# MCU.net
KiCad netlist of a schematic drawn in Altium Designer
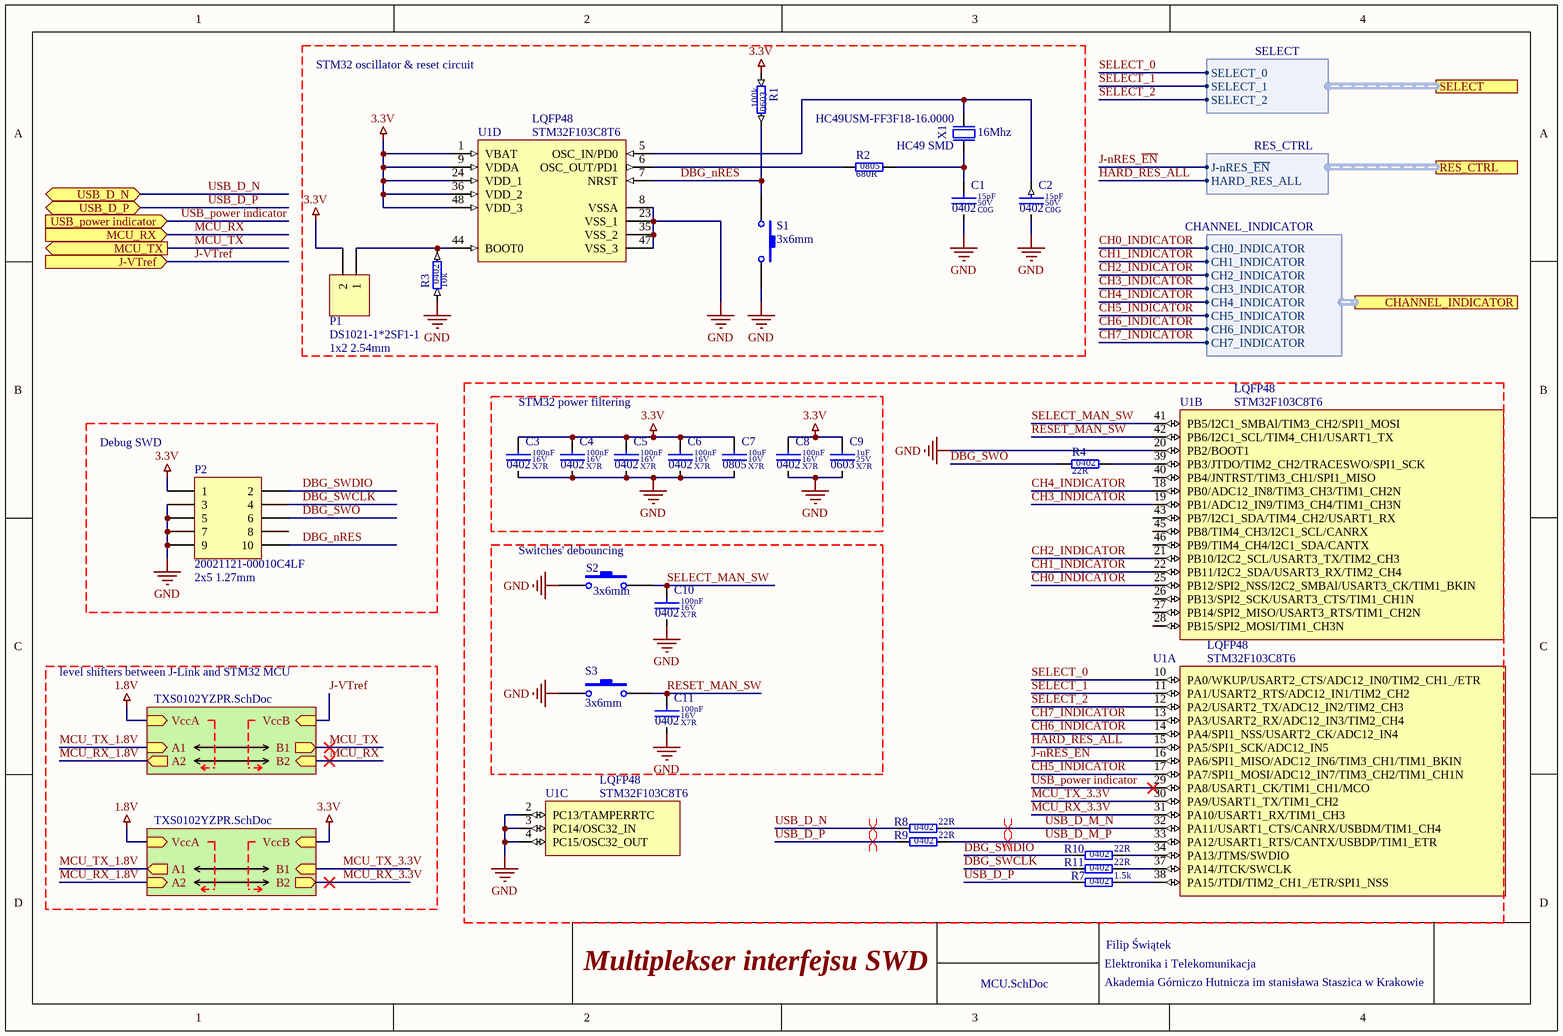
[diagram p0: MCU.SchDoc]

(export (version "E")
  (design (tool "Eeschema 10.0.6"))
  (components
    (comp (ref "C1")
      (value "15pF")
      (footprint "C_0402_1005")
      (description "Capacitor")
      (fields
        (field (name "DIELECTRIC") "C0G")
        (field (name "VOLTAGE") "50V")
        (field (name "SCH_FOOTPRINT") "0402")
        (field (name "PART NUMBER") "C_15pF_50V_C0G_0402_5")
        (field (name "MANUFACTURER") "Murata")
      )
      (libsource (lib "Library") (part "C"))
    )
    (comp (ref "C2")
      (value "15pF")
      (footprint "C_0402_1005")
      (description "Capacitor")
      (fields
        (field (name "DIELECTRIC") "C0G")
        (field (name "VOLTAGE") "50V")
        (field (name "SCH_FOOTPRINT") "0402")
        (field (name "PART NUMBER") "C_15pF_50V_C0G_0402_5")
        (field (name "MANUFACTURER") "Murata")
      )
      (libsource (lib "") (part "C_1"))
    )
    (comp (ref "C3")
      (value "100nF")
      (footprint "C_0402_1005")
      (description "Capacitor")
      (fields
        (field (name "DIELECTRIC") "X7R")
        (field (name "VOLTAGE") "16V")
        (field (name "SCH_FOOTPRINT") "0402")
        (field (name "PART NUMBER") "C_100nF_16V_X7R_0402_10")
        (field (name "MANUFACTURER") "Murata")
      )
      (libsource (lib "Library") (part "C"))
    )
    (comp (ref "C4")
      (value "100nF")
      (footprint "C_0402_1005")
      (description "Capacitor")
      (fields
        (field (name "DIELECTRIC") "X7R")
        (field (name "VOLTAGE") "16V")
        (field (name "SCH_FOOTPRINT") "0402")
        (field (name "PART NUMBER") "C_100nF_16V_X7R_0402_10")
        (field (name "MANUFACTURER") "Murata")
      )
      (libsource (lib "Library") (part "C"))
    )
    (comp (ref "C5")
      (value "100nF")
      (footprint "C_0402_1005")
      (description "Capacitor")
      (fields
        (field (name "DIELECTRIC") "X7R")
        (field (name "VOLTAGE") "16V")
        (field (name "SCH_FOOTPRINT") "0402")
        (field (name "PART NUMBER") "C_100nF_16V_X7R_0402_10")
        (field (name "MANUFACTURER") "Murata")
      )
      (libsource (lib "Library") (part "C"))
    )
    (comp (ref "C6")
      (value "100nF")
      (footprint "C_0402_1005")
      (description "Capacitor")
      (fields
        (field (name "DIELECTRIC") "X7R")
        (field (name "VOLTAGE") "16V")
        (field (name "SCH_FOOTPRINT") "0402")
        (field (name "PART NUMBER") "C_100nF_16V_X7R_0402_10")
        (field (name "MANUFACTURER") "Murata")
      )
      (libsource (lib "Library") (part "C"))
    )
    (comp (ref "C7")
      (value "10uF")
      (footprint "C_0805_2012")
      (description "Capacitor")
      (fields
        (field (name "DIELECTRIC") "X7R")
        (field (name "VOLTAGE") "10V")
        (field (name "SCH_FOOTPRINT") "0805")
        (field (name "PART NUMBER") "C_10uF_10V_X7R_0805_10")
        (field (name "MANUFACTURER") "Samsung Electro-Mechanics")
      )
      (libsource (lib "Library") (part "C"))
    )
    (comp (ref "C8")
      (value "100nF")
      (footprint "C_0402_1005")
      (description "Capacitor")
      (fields
        (field (name "DIELECTRIC") "X7R")
        (field (name "VOLTAGE") "16V")
        (field (name "SCH_FOOTPRINT") "0402")
        (field (name "PART NUMBER") "C_100nF_16V_X7R_0402_10")
        (field (name "MANUFACTURER") "Murata")
      )
      (libsource (lib "Library") (part "C"))
    )
    (comp (ref "C9")
      (value "1uF")
      (footprint "C_0603_1608")
      (description "Capacitor")
      (fields
        (field (name "DIELECTRIC") "X7R")
        (field (name "VOLTAGE") "25V")
        (field (name "SCH_FOOTPRINT") "0603")
        (field (name "PART NUMBER") "C_1uF_25V_X7R_0603_10")
        (field (name "MANUFACTURER") "Samsung")
      )
      (libsource (lib "Library") (part "C"))
    )
    (comp (ref "C10")
      (value "100nF")
      (footprint "C_0402_1005")
      (description "Capacitor")
      (fields
        (field (name "DIELECTRIC") "X7R")
        (field (name "VOLTAGE") "16V")
        (field (name "SCH_FOOTPRINT") "0402")
        (field (name "PART NUMBER") "C_100nF_16V_X7R_0402_10")
        (field (name "MANUFACTURER") "Murata")
      )
      (libsource (lib "Library") (part "C"))
    )
    (comp (ref "C11")
      (value "100nF")
      (footprint "C_0402_1005")
      (description "Capacitor")
      (fields
        (field (name "DIELECTRIC") "X7R")
        (field (name "VOLTAGE") "16V")
        (field (name "SCH_FOOTPRINT") "0402")
        (field (name "PART NUMBER") "C_100nF_16V_X7R_0402_10")
        (field (name "MANUFACTURER") "Murata")
      )
      (libsource (lib "Library") (part "C"))
    )
    (comp (ref "P1")
      (value "DS1021-1*2SF1-1")
      (footprint "P_HEADER_1x2_2.54")
      (description "Header, 2-Pin")
      (fields
        (field (name "PART NUMBER") "P_HEADER_1x2_2.54")
        (field (name "SCH_FOOTPRINT") "1x2 2.54mm")
        (field (name "MANUFACTURER") "Connfly")
      )
      (libsource (lib "Library") (part "P_HEADER_1x2"))
    )
    (comp (ref "P2")
      (value "20021121-00010C4LF")
      (footprint "P_HEADER_2x5_1.27")
      (description "Header, 10-Pin, Dual row")
      (fields
        (field (name "PART NUMBER") "P_HEADER_2x5_1.27")
        (field (name "SCH_FOOTPRINT") "2x5 1.27mm")
        (field (name "MANUFACTURER") "FCI")
      )
      (libsource (lib "Library") (part "P_HEADER_2x5"))
    )
    (comp (ref "R1")
      (value "100k")
      (footprint "R_0603_1608")
      (fields
        (field (name "SCH_FOOTPRINT") "0603")
        (field (name "PART NUMBER") "R_100k_0603_1")
        (field (name "VOLTAGE") "50V")
        (field (name "POWER") "100mW")
      )
      (libsource (lib "") (part "R_1"))
    )
    (comp (ref "R2")
      (value "680R")
      (footprint "R_0805_2012")
      (fields
        (field (name "SCH_FOOTPRINT") "0805")
        (field (name "PART NUMBER") "R_680R_0805_1")
        (field (name "VOLTAGE") "150V")
        (field (name "POWER") "300mW")
      )
      (libsource (lib "Library") (part "R"))
    )
    (comp (ref "R3")
      (value "10k")
      (footprint "R_0402_1005")
      (fields
        (field (name "SCH_FOOTPRINT") "0402")
        (field (name "PART NUMBER") "R_10k_0402_1")
        (field (name "VOLTAGE") "50V")
        (field (name "POWER") "63mW")
      )
      (libsource (lib "") (part "R_1"))
    )
    (comp (ref "R4")
      (value "22R")
      (footprint "R_0402_1005")
      (fields
        (field (name "SCH_FOOTPRINT") "0402")
        (field (name "PART NUMBER") "R_22R_0402_1")
        (field (name "VOLTAGE") "50V")
        (field (name "POWER") "63mW")
      )
      (libsource (lib "Library") (part "R"))
    )
    (comp (ref "R7")
      (value "1.5k")
      (footprint "R_NC_0402_1005")
      (fields
        (field (name "SCH_FOOTPRINT") "0402")
        (field (name "PART NUMBER") "R_GENERIC_0402")
        (field (name "Comment") "Resistor")
      )
      (libsource (lib "Library") (part "R"))
    )
    (comp (ref "R8")
      (value "22R")
      (footprint "R_0402_1005")
      (fields
        (field (name "SCH_FOOTPRINT") "0402")
        (field (name "PART NUMBER") "R_22R_0402_1")
        (field (name "VOLTAGE") "50V")
        (field (name "POWER") "63mW")
      )
      (libsource (lib "Library") (part "R"))
    )
    (comp (ref "R9")
      (value "22R")
      (footprint "R_0402_1005")
      (fields
        (field (name "SCH_FOOTPRINT") "0402")
        (field (name "PART NUMBER") "R_22R_0402_1")
        (field (name "VOLTAGE") "50V")
        (field (name "POWER") "63mW")
      )
      (libsource (lib "Library") (part "R"))
    )
    (comp (ref "R10")
      (value "22R")
      (footprint "R_0402_1005")
      (fields
        (field (name "SCH_FOOTPRINT") "0402")
        (field (name "PART NUMBER") "R_22R_0402_1")
        (field (name "VOLTAGE") "50V")
        (field (name "POWER") "63mW")
      )
      (libsource (lib "Library") (part "R"))
    )
    (comp (ref "R11")
      (value "22R")
      (footprint "R_0402_1005")
      (fields
        (field (name "SCH_FOOTPRINT") "0402")
        (field (name "PART NUMBER") "R_22R_0402_1")
        (field (name "VOLTAGE") "50V")
        (field (name "POWER") "63mW")
      )
      (libsource (lib "Library") (part "R"))
    )
    (comp (ref "S1")
      (value "3x6mm")
      (footprint "S_TACTSWITCH3x6")
      (description "Tact Switch")
      (fields
        (field (name "PART NUMBER") "S_TACTSWITCH")
        (field (name "SCH_FOOTPRINT") "3x6mm")
        (field (name "MANUFACTURER") "Ninigi")
      )
      (libsource (lib "Library") (part "S_TACTSWITCH"))
    )
    (comp (ref "S2")
      (value "3x6mm")
      (footprint "S_TACTSWITCH3x6")
      (description "Tact Switch")
      (fields
        (field (name "PART NUMBER") "S_TACTSWITCH")
        (field (name "SCH_FOOTPRINT") "3x6mm")
        (field (name "MANUFACTURER") "Ninigi")
      )
      (libsource (lib "Library") (part "S_TACTSWITCH"))
    )
    (comp (ref "S3")
      (value "3x6mm")
      (footprint "S_TACTSWITCH3x6")
      (description "Tact Switch")
      (fields
        (field (name "PART NUMBER") "S_TACTSWITCH")
        (field (name "SCH_FOOTPRINT") "3x6mm")
        (field (name "MANUFACTURER") "Ninigi")
      )
      (libsource (lib "Library") (part "S_TACTSWITCH"))
    )
    (comp (ref "U1")
      (value "STM32F103C8T6")
      (footprint "LQFP48_7x7")
      (fields
        (field (name "SCH_FOOTPRINT") "LQFP48")
        (field (name "PART NUMBER") "UP_STM32F103C8T6")
        (field (name "MANUFACTURER") "STMicroelectronics")
      )
      (libsource (lib "Library") (part "UP_STM32F103Cx"))
    )
    (comp (ref "X1")
      (value "16Mhz")
      (footprint "X_HC49_SMD")
      (description "Resonator Ceramic")
      (fields
        (field (name "PART NUMBER") "X_HC49USM-FF3F16.00")
        (field (name "MANUFACTURER PART NUMBER") "HC49USM-FF3F18-16.0000")
        (field (name "SCH_FOOTPRINT") "HC49 SMD")
        (field (name "MANUFACTURER") "Ilsi")
      )
      (libsource (lib "Library") (part "X_GENERIC"))
    )
  )
  (nets
    (net (code "6") (name "/CH0_INDICATOR") (class "Default")
      (node (ref "U1") (pin "25") (pinfunction "PB12/SPI2_NSS/I2C2_SMBAl/USART3_CK/TIM1_BKIN_25") (pintype "bidirectional"))
    )
    (net (code "7") (name "/CH1_INDICATOR") (class "Default")
      (node (ref "U1") (pin "22") (pinfunction "PB11/I2C2_SDA/USART3_RX/TIM2_CH4_22") (pintype "bidirectional"))
    )
    (net (code "8") (name "/CH2_INDICATOR") (class "Default")
      (node (ref "U1") (pin "21") (pinfunction "PB10/I2C2_SCL/USART3_TX/TIM2_CH3_21") (pintype "bidirectional"))
    )
    (net (code "9") (name "/CH3_INDICATOR") (class "Default")
      (node (ref "U1") (pin "19") (pinfunction "PB1/ADC12_IN9/TIM3_CH4/TIM1_CH3N_19") (pintype "bidirectional"))
    )
    (net (code "10") (name "/CH4_INDICATOR") (class "Default")
      (node (ref "U1") (pin "18") (pinfunction "PB0/ADC12_IN8/TIM3_CH3/TIM1_CH2N_18") (pintype "bidirectional"))
    )
    (net (code "11") (name "/CH5_INDICATOR") (class "Default")
      (node (ref "U1") (pin "17") (pinfunction "PA7/SPI1_MOSI/ADC12_IN7/TIM3_CH2/TIM1_CH1N_17") (pintype "bidirectional"))
    )
    (net (code "12") (name "/CH6_INDICATOR") (class "Default")
      (node (ref "U1") (pin "14") (pinfunction "PA4/SPI1_NSS/USART2_CK/ADC12_IN4_14") (pintype "bidirectional"))
    )
    (net (code "13") (name "/CH7_INDICATOR") (class "Default")
      (node (ref "U1") (pin "13") (pinfunction "PA3/USART2_RX/ADC12_IN3/TIM2_CH4_13") (pintype "bidirectional"))
    )
    (net (code "14") (name "/DBG_SWCLK") (class "Default")
      (node (ref "P2") (pin "4") (pinfunction "4_4") (pintype "passive"))
      (node (ref "R11") (pin "1") (pinfunction "1_1") (pintype "passive"))
    )
    (net (code "15") (name "/DBG_SWDIO") (class "Default")
      (node (ref "P2") (pin "2") (pinfunction "2_2") (pintype "passive"))
      (node (ref "R10") (pin "1") (pinfunction "1_1") (pintype "passive"))
    )
    (net (code "16") (name "/DBG_SWO") (class "Default")
      (node (ref "P2") (pin "6") (pinfunction "6_6") (pintype "passive"))
      (node (ref "R4") (pin "1") (pinfunction "1_1") (pintype "passive"))
    )
    (net (code "17") (name "/DBG_nRES") (class "Default")
      (node (ref "P2") (pin "10") (pinfunction "10_10") (pintype "passive"))
      (node (ref "R1") (pin "2") (pinfunction "2_2") (pintype "output"))
      (node (ref "S1") (pin "1") (pinfunction "1_1") (pintype "passive"))
      (node (ref "U1") (pin "7") (pinfunction "NRST_7") (pintype "input"))
    )
    (net (code "18") (name "/HARD_RES_ALL") (class "Default")
      (node (ref "U1") (pin "15") (pinfunction "PA5/SPI1_SCK/ADC12_IN5_15") (pintype "bidirectional"))
    )
    (net (code "20") (name "/J-nRES_~{EN}") (class "Default")
      (node (ref "U1") (pin "16") (pinfunction "PA6/SPI1_MISO/ADC12_IN6/TIM3_CH1/TIM1_BKIN_16") (pintype "bidirectional"))
    )
    (net (code "23") (name "/MCU_RX_3.3V") (class "Default")
      (node (ref "U1") (pin "31") (pinfunction "PA10/USART1_RX/TIM1_CH3_31") (pintype "bidirectional"))
    )
    (net (code "26") (name "/MCU_TX_3.3V") (class "Default")
      (node (ref "U1") (pin "30") (pinfunction "PA9/USART1_TX/TIM1_CH2_30") (pintype "bidirectional"))
    )
    (net (code "27") (name "/RESET_MAN_SW") (class "Default")
      (node (ref "C11") (pin "1") (pinfunction "1_1") (pintype "passive"))
      (node (ref "S3") (pin "2") (pinfunction "2_2") (pintype "passive"))
      (node (ref "U1") (pin "42") (pinfunction "PB6/I2C1_SCL/TIM4_CH1/USART1_TX_42") (pintype "bidirectional"))
    )
    (net (code "28") (name "/SELECT_0") (class "Default")
      (node (ref "U1") (pin "10") (pinfunction "PA0/WKUP/USART2_CTS/ADC12_IN0/TIM2_CH1_/ETR_10") (pintype "bidirectional"))
    )
    (net (code "29") (name "/SELECT_1") (class "Default")
      (node (ref "U1") (pin "11") (pinfunction "PA1/USART2_RTS/ADC12_IN1/TIM2_CH2_11") (pintype "bidirectional"))
    )
    (net (code "30") (name "/SELECT_2") (class "Default")
      (node (ref "U1") (pin "12") (pinfunction "PA2/USART2_TX/ADC12_IN2/TIM2_CH3_12") (pintype "bidirectional"))
    )
    (net (code "31") (name "/SELECT_MAN_SW") (class "Default")
      (node (ref "C10") (pin "1") (pinfunction "1_1") (pintype "passive"))
      (node (ref "S2") (pin "2") (pinfunction "2_2") (pintype "passive"))
      (node (ref "U1") (pin "41") (pinfunction "PB5/I2C1_SMBAl/TIM3_CH2/SPI1_MOSI_41") (pintype "bidirectional"))
    )
    (net (code "32") (name "/USB_D_M_N") (class "Default")
      (node (ref "R8") (pin "2") (pinfunction "2_2") (pintype "passive"))
      (node (ref "U1") (pin "32") (pinfunction "PA11/USART1_CTS/CANRX/USBDM/TIM1_CH4_32") (pintype "bidirectional"))
    )
    (net (code "33") (name "/USB_D_M_P") (class "Default")
      (node (ref "R9") (pin "2") (pinfunction "2_2") (pintype "passive"))
      (node (ref "U1") (pin "33") (pinfunction "PA12/USART1_RTS/CANTX/USBDP/TIM1_ETR_33") (pintype "bidirectional"))
    )
    (net (code "34") (name "/USB_D_N") (class "Default")
      (node (ref "R8") (pin "1") (pinfunction "1_1") (pintype "passive"))
    )
    (net (code "35") (name "/USB_D_P") (class "Default")
      (node (ref "R7") (pin "1") (pinfunction "1_1") (pintype "passive"))
      (node (ref "R9") (pin "1") (pinfunction "1_1") (pintype "passive"))
    )
    (net (code "36") (name "/USB_power indicator") (class "Default")
      (node (ref "U1") (pin "29") (pinfunction "PA8/USART1_CK/TIM1_CH1/MCO_29") (pintype "bidirectional"))
    )
    (net (code "41") (name "3.3V") (class "Default")
      (node (ref "C3") (pin "1") (pinfunction "1_1") (pintype "passive"))
      (node (ref "C4") (pin "1") (pinfunction "1_1") (pintype "passive"))
      (node (ref "C5") (pin "1") (pinfunction "1_1") (pintype "passive"))
      (node (ref "C6") (pin "1") (pinfunction "1_1") (pintype "passive"))
      (node (ref "C7") (pin "1") (pinfunction "1_1") (pintype "passive"))
      (node (ref "C8") (pin "1") (pinfunction "1_1") (pintype "passive"))
      (node (ref "C9") (pin "1") (pinfunction "1_1") (pintype "passive"))
      (node (ref "P1") (pin "2") (pinfunction "2_2") (pintype "passive"))
      (node (ref "P2") (pin "1") (pinfunction "1_1") (pintype "passive"))
      (node (ref "R1") (pin "1") (pinfunction "1_1") (pintype "input"))
      (node (ref "U1") (pin "1") (pinfunction "VBAT_1") (pintype "input"))
      (node (ref "U1") (pin "24") (pinfunction "VDD_1_24") (pintype "input"))
      (node (ref "U1") (pin "36") (pinfunction "VDD_2_36") (pintype "input"))
      (node (ref "U1") (pin "48") (pinfunction "VDD_3_48") (pintype "input"))
      (node (ref "U1") (pin "9") (pinfunction "VDDA_9") (pintype "input"))
    )
    (net (code "42") (name "GND") (class "Default")
      (node (ref "C1") (pin "2") (pinfunction "2_2") (pintype "passive"))
      (node (ref "C10") (pin "2") (pinfunction "2_2") (pintype "passive"))
      (node (ref "C11") (pin "2") (pinfunction "2_2") (pintype "passive"))
      (node (ref "C2") (pin "2") (pinfunction "2_2") (pintype "input"))
      (node (ref "C3") (pin "2") (pinfunction "2_2") (pintype "passive"))
      (node (ref "C4") (pin "2") (pinfunction "2_2") (pintype "passive"))
      (node (ref "C5") (pin "2") (pinfunction "2_2") (pintype "passive"))
      (node (ref "C6") (pin "2") (pinfunction "2_2") (pintype "passive"))
      (node (ref "C7") (pin "2") (pinfunction "2_2") (pintype "passive"))
      (node (ref "C8") (pin "2") (pinfunction "2_2") (pintype "passive"))
      (node (ref "C9") (pin "2") (pinfunction "2_2") (pintype "passive"))
      (node (ref "P2") (pin "3") (pinfunction "3_3") (pintype "passive"))
      (node (ref "P2") (pin "5") (pinfunction "5_5") (pintype "passive"))
      (node (ref "P2") (pin "7") (pinfunction "7_7") (pintype "passive"))
      (node (ref "P2") (pin "9") (pinfunction "9_9") (pintype "passive"))
      (node (ref "R3") (pin "1") (pinfunction "1_1") (pintype "input"))
      (node (ref "S1") (pin "2") (pinfunction "2_2") (pintype "passive"))
      (node (ref "S2") (pin "1") (pinfunction "1_1") (pintype "passive"))
      (node (ref "S3") (pin "1") (pinfunction "1_1") (pintype "passive"))
      (node (ref "U1") (pin "2") (pinfunction "PC13/TAMPERRTC_2") (pintype "bidirectional"))
      (node (ref "U1") (pin "20") (pinfunction "PB2/BOOT1_20") (pintype "bidirectional"))
      (node (ref "U1") (pin "23") (pinfunction "VSS_1_23") (pintype "power_in"))
      (node (ref "U1") (pin "3") (pinfunction "PC14/OSC32_IN_3") (pintype "bidirectional"))
      (node (ref "U1") (pin "35") (pinfunction "VSS_2_35") (pintype "power_in"))
      (node (ref "U1") (pin "4") (pinfunction "PC15/OSC32_OUT_4") (pintype "bidirectional"))
      (node (ref "U1") (pin "47") (pinfunction "VSS_3_47") (pintype "power_in"))
      (node (ref "U1") (pin "8") (pinfunction "VSSA_8") (pintype "power_in"))
    )
    (net (code "43") (name "Net-(C1-Pad1)") (class "Default")
      (node (ref "C1") (pin "1") (pinfunction "1_1") (pintype "passive"))
      (node (ref "R2") (pin "2") (pinfunction "2_2") (pintype "passive"))
      (node (ref "X1") (pin "1") (pintype "passive"))
    )
    (net (code "44") (name "Net-(U1A-PA13{slash}JTMS{slash}SWDIO)") (class "Default")
      (node (ref "R10") (pin "2") (pinfunction "2_2") (pintype "passive"))
      (node (ref "U1") (pin "34") (pinfunction "PA13/JTMS/SWDIO_34") (pintype "bidirectional"))
    )
    (net (code "45") (name "Net-(U1A-PA14{slash}JTCK{slash}SWCLK)") (class "Default")
      (node (ref "R11") (pin "2") (pinfunction "2_2") (pintype "passive"))
      (node (ref "U1") (pin "37") (pinfunction "PA14/JTCK/SWCLK_37") (pintype "bidirectional"))
    )
    (net (code "46") (name "Net-(U1A-PA15{slash}JTDI{slash}TIM2_CH1_{slash}ETR{slash}SPI1_NSS)") (class "Default")
      (node (ref "R7") (pin "2") (pinfunction "2_2") (pintype "passive"))
      (node (ref "U1") (pin "38") (pinfunction "PA15/JTDI/TIM2_CH1_/ETR/SPI1_NSS_38") (pintype "bidirectional"))
    )
    (net (code "47") (name "Net-(U1B-PB3{slash}JTDO{slash}TIM2_CH2{slash}TRACESWO{slash}SPI1_SCK)") (class "Default")
      (node (ref "R4") (pin "2") (pinfunction "2_2") (pintype "passive"))
      (node (ref "U1") (pin "39") (pinfunction "PB3/JTDO/TIM2_CH2/TRACESWO/SPI1_SCK_39") (pintype "bidirectional"))
    )
    (net (code "48") (name "Net-(U1D-BOOT0)") (class "Default")
      (node (ref "P1") (pin "1") (pinfunction "1_1") (pintype "passive"))
      (node (ref "R3") (pin "2") (pinfunction "2_2") (pintype "output"))
      (node (ref "U1") (pin "44") (pinfunction "BOOT0_44") (pintype "input"))
    )
    (net (code "49") (name "Net-(U1D-OSC_IN{slash}PD0)") (class "Default")
      (node (ref "C2") (pin "1") (pinfunction "1_1") (pintype "output"))
      (node (ref "U1") (pin "5") (pinfunction "OSC_IN/PD0_5") (pintype "input"))
      (node (ref "X1") (pin "2") (pintype "passive"))
    )
    (net (code "50") (name "Net-(U1D-OSC_OUT{slash}PD1)") (class "Default")
      (node (ref "R2") (pin "1") (pinfunction "1_1") (pintype "passive"))
      (node (ref "U1") (pin "6") (pinfunction "OSC_OUT/PD1_6") (pintype "output"))
    )
    (net (code "51") (name "unconnected-(P2-Pad8)") (class "Default")
      (node (ref "P2") (pin "8") (pinfunction "8_8") (pintype "passive"))
    )
    (net (code "52") (name "unconnected-(U1B-PB4{slash}JNTRST{slash}TIM3_CH1{slash}SPI1_MISO-Pad40)") (class "Default")
      (node (ref "U1") (pin "40") (pinfunction "PB4/JNTRST/TIM3_CH1/SPI1_MISO_40") (pintype "bidirectional"))
    )
    (net (code "53") (name "unconnected-(U1B-PB7{slash}I2C1_SDA{slash}TIM4_CH2{slash}USART1_RX-Pad43)") (class "Default")
      (node (ref "U1") (pin "43") (pinfunction "PB7/I2C1_SDA/TIM4_CH2/USART1_RX_43") (pintype "bidirectional"))
    )
    (net (code "54") (name "unconnected-(U1B-PB8{slash}TIM4_CH3{slash}I2C1_SCL{slash}CANRX-Pad45)") (class "Default")
      (node (ref "U1") (pin "45") (pinfunction "PB8/TIM4_CH3/I2C1_SCL/CANRX_45") (pintype "bidirectional"))
    )
    (net (code "55") (name "unconnected-(U1B-PB9{slash}TIM4_CH4{slash}I2C1_SDA{slash}CANTX-Pad46)") (class "Default")
      (node (ref "U1") (pin "46") (pinfunction "PB9/TIM4_CH4/I2C1_SDA/CANTX_46") (pintype "bidirectional"))
    )
    (net (code "56") (name "unconnected-(U1B-PB13{slash}SPI2_SCK{slash}USART3_CTS{slash}TIM1_CH1N-Pad26)") (class "Default")
      (node (ref "U1") (pin "26") (pinfunction "PB13/SPI2_SCK/USART3_CTS/TIM1_CH1N_26") (pintype "bidirectional"))
    )
    (net (code "57") (name "unconnected-(U1B-PB14{slash}SPI2_MISO{slash}USART3_RTS{slash}TIM1_CH2N-Pad27)") (class "Default")
      (node (ref "U1") (pin "27") (pinfunction "PB14/SPI2_MISO/USART3_RTS/TIM1_CH2N_27") (pintype "bidirectional"))
    )
    (net (code "58") (name "unconnected-(U1B-PB15{slash}SPI2_MOSI{slash}TIM1_CH3N-Pad28)") (class "Default")
      (node (ref "U1") (pin "28") (pinfunction "PB15/SPI2_MOSI/TIM1_CH3N_28") (pintype "bidirectional"))
    )
  )
)
